# PLC1_4.net
KiCad netlist of a schematic drawn in Altium Designer
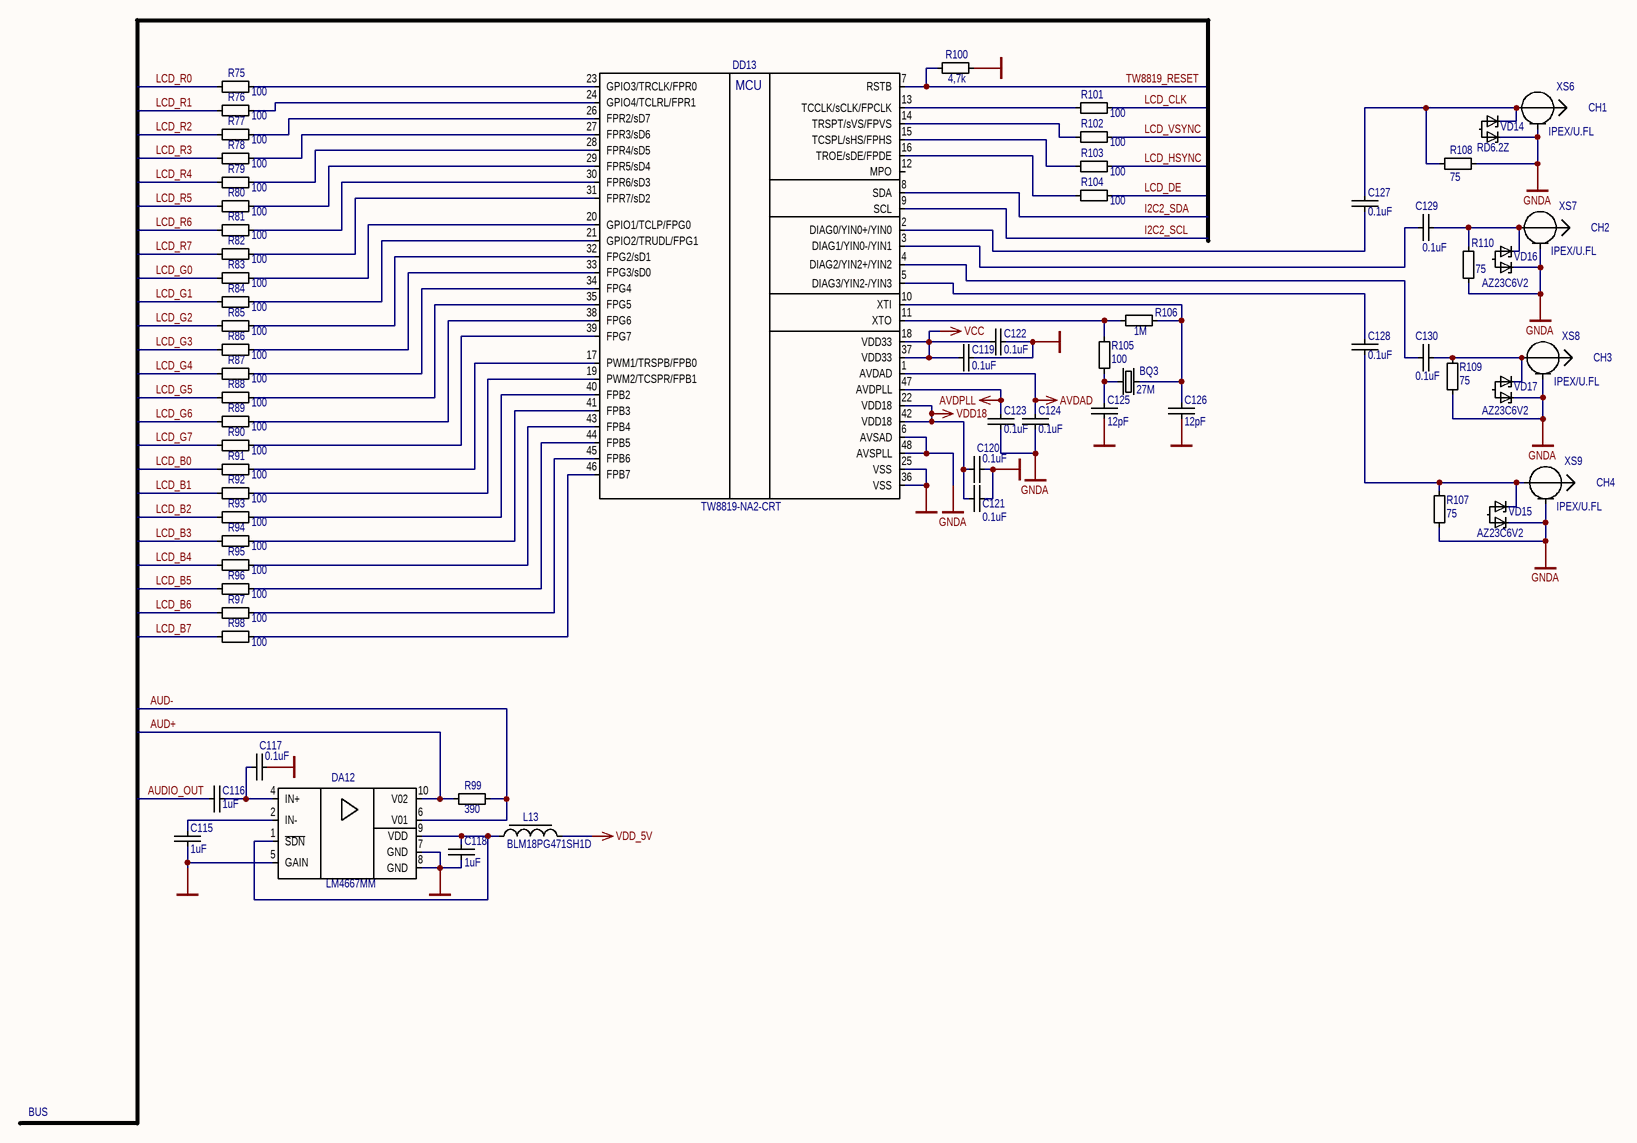
[diagram p0: PLC1_4.SchDoc]

(export (version "E")
  (design (tool "Eeschema 10.0.6"))
  (components
    (comp (ref "BQ3")
      (value "27M")
      (footprint "TSX-3225")
      (fields
        (field (name "MANUFACTURER") "EPSON")
        (field (name "PART NUMBER") "EPSON TSX-3225 27.0000MF10Z-K3")
        (field (name "Comment") "TSX-3225")
      )
      (libsource (lib "PLC1") (part "TSX-3225"))
    )
    (comp (ref "C115")
      (value "1uF")
      (footprint "CAP_0603")
      (fields (field (name "MANUFACTURER") "AVX") (field (name "PART NUMBER") "0603YC105KAT2A"))
      (libsource (lib "PLC1") (part "Cap_0603"))
    )
    (comp (ref "C116")
      (value "1uF")
      (footprint "CAP_0603")
      (fields (field (name "MANUFACTURER") "AVX") (field (name "PART NUMBER") "0603YC105KAT2A"))
      (libsource (lib "PLC1") (part "Cap_0603"))
    )
    (comp (ref "C117")
      (value "0.1uF")
      (footprint "CAP_0603")
      (fields (field (name "MANUFACTURER") "AVX") (field (name "PART NUMBER") "0603YC104KAT2A"))
      (libsource (lib "PLC1") (part "Cap_0603"))
    )
    (comp (ref "C118")
      (value "1uF")
      (footprint "CAP_0603")
      (fields (field (name "MANUFACTURER") "AVX") (field (name "PART NUMBER") "0603YC105KAT2A"))
      (libsource (lib "PLC1") (part "Cap_0603"))
    )
    (comp (ref "C119")
      (value "0.1uF")
      (footprint "CAP_0603")
      (fields (field (name "MANUFACTURER") "AVX") (field (name "PART NUMBER") "0603YC104KAT2A"))
      (libsource (lib "PLC1") (part "Cap_0603"))
    )
    (comp (ref "C120")
      (value "0.1uF")
      (footprint "CAP_0603")
      (fields (field (name "MANUFACTURER") "AVX") (field (name "PART NUMBER") "0603YC104KAT2A"))
      (libsource (lib "PLC1") (part "Cap_0603"))
    )
    (comp (ref "C121")
      (value "0.1uF")
      (footprint "CAP_0603")
      (fields (field (name "MANUFACTURER") "AVX") (field (name "PART NUMBER") "0603YC104KAT2A"))
      (libsource (lib "PLC1") (part "Cap_0603"))
    )
    (comp (ref "C122")
      (value "0.1uF")
      (footprint "CAP_0603")
      (fields (field (name "MANUFACTURER") "AVX") (field (name "PART NUMBER") "0603YC104KAT2A"))
      (libsource (lib "PLC1") (part "Cap_0603"))
    )
    (comp (ref "C123")
      (value "0.1uF")
      (footprint "CAP_0603")
      (fields (field (name "MANUFACTURER") "AVX") (field (name "PART NUMBER") "0603YC104KAT2A"))
      (libsource (lib "PLC1") (part "Cap_0603"))
    )
    (comp (ref "C124")
      (value "0.1uF")
      (footprint "CAP_0603")
      (fields (field (name "MANUFACTURER") "AVX") (field (name "PART NUMBER") "0603YC104KAT2A"))
      (libsource (lib "PLC1") (part "Cap_0603"))
    )
    (comp (ref "C125")
      (value "12pF")
      (footprint "CAP_0603")
      (fields (field (name "MANUFACTURER") "Murata") (field (name "PART NUMBER") "GRM1885C1H120JA01D"))
      (libsource (lib "PLC1") (part "Cap_0603"))
    )
    (comp (ref "C126")
      (value "12pF")
      (footprint "CAP_0603")
      (fields (field (name "MANUFACTURER") "Murata") (field (name "PART NUMBER") "GRM1885C1H120JA01D"))
      (libsource (lib "PLC1") (part "Cap_0603"))
    )
    (comp (ref "C127")
      (value "0.1uF")
      (footprint "CAP_0603")
      (fields (field (name "MANUFACTURER") "AVX") (field (name "PART NUMBER") "0603YC104KAT2A"))
      (libsource (lib "PLC1") (part "Cap_0603"))
    )
    (comp (ref "C128")
      (value "0.1uF")
      (footprint "CAP_0603")
      (fields (field (name "MANUFACTURER") "AVX") (field (name "PART NUMBER") "0603YC104KAT2A"))
      (libsource (lib "PLC1") (part "Cap_0603"))
    )
    (comp (ref "C129")
      (value "0.1uF")
      (footprint "CAP_0603")
      (fields (field (name "MANUFACTURER") "AVX") (field (name "PART NUMBER") "0603YC104KAT2A"))
      (libsource (lib "PLC1") (part "Cap_0603"))
    )
    (comp (ref "C130")
      (value "0.1uF")
      (footprint "CAP_0603")
      (fields (field (name "MANUFACTURER") "AVX") (field (name "PART NUMBER") "0603YC104KAT2A"))
      (libsource (lib "PLC1") (part "Cap_0603"))
    )
    (comp (ref "DA12")
      (value "LM4667MM")
      (footprint "S-PDSO-G10")
      (description "LM4667MM/NOPB")
      (fields (field (name "MANUFACTURER") "TEXAS INSTRUMENTS"))
      (libsource (lib "PLC1") (part "LM4667MM/NOPB"))
    )
    (comp (ref "DD13")
      (value "TW8819-NA2-CRT")
      (footprint "QFN48.7x7")
      (fields (field (name "MANUFACTURER") "Intersil") (field (name "TW8819-NA2-CRT") "TW8819-NA2-CRT"))
      (libsource (lib "PLC1") (part "TW8819-NA2-CRT"))
    )
    (comp (ref "L13")
      (value "BLM18PG471SH1D")
      (footprint "R_IND_0603")
      (fields (field (name "MANUFACTURER") "Murata"))
      (libsource (lib "PLC1") (part "FCM1608KF-601T03"))
    )
    (comp (ref "R75")
      (value "100")
      (footprint "RES_0402")
      (description "0402")
      (fields (field (name "MANUFACTURER") "BOURNS") (field (name "PART NUMBER") "CR0402-FX-1000GLF"))
      (libsource (lib "PLC1") (part "Res_0402"))
    )
    (comp (ref "R76")
      (value "100")
      (footprint "RES_0402")
      (description "0402")
      (fields (field (name "MANUFACTURER") "BOURNS") (field (name "PART NUMBER") "CR0402-FX-1000GLF"))
      (libsource (lib "PLC1") (part "Res_0402"))
    )
    (comp (ref "R77")
      (value "100")
      (footprint "RES_0402")
      (description "0402")
      (fields (field (name "MANUFACTURER") "BOURNS") (field (name "PART NUMBER") "CR0402-FX-1000GLF"))
      (libsource (lib "PLC1") (part "Res_0402"))
    )
    (comp (ref "R78")
      (value "100")
      (footprint "RES_0402")
      (description "0402")
      (fields (field (name "MANUFACTURER") "BOURNS") (field (name "PART NUMBER") "CR0402-FX-1000GLF"))
      (libsource (lib "PLC1") (part "Res_0402"))
    )
    (comp (ref "R79")
      (value "100")
      (footprint "RES_0402")
      (description "0402")
      (fields (field (name "MANUFACTURER") "BOURNS") (field (name "PART NUMBER") "CR0402-FX-1000GLF"))
      (libsource (lib "PLC1") (part "Res_0402"))
    )
    (comp (ref "R80")
      (value "100")
      (footprint "RES_0402")
      (description "0402")
      (fields (field (name "MANUFACTURER") "BOURNS") (field (name "PART NUMBER") "CR0402-FX-1000GLF"))
      (libsource (lib "PLC1") (part "Res_0402"))
    )
    (comp (ref "R81")
      (value "100")
      (footprint "RES_0402")
      (description "0402")
      (fields (field (name "MANUFACTURER") "BOURNS") (field (name "PART NUMBER") "CR0402-FX-1000GLF"))
      (libsource (lib "PLC1") (part "Res_0402"))
    )
    (comp (ref "R82")
      (value "100")
      (footprint "RES_0402")
      (description "0402")
      (fields (field (name "MANUFACTURER") "BOURNS") (field (name "PART NUMBER") "CR0402-FX-1000GLF"))
      (libsource (lib "PLC1") (part "Res_0402"))
    )
    (comp (ref "R83")
      (value "100")
      (footprint "RES_0402")
      (description "0402")
      (fields (field (name "MANUFACTURER") "BOURNS") (field (name "PART NUMBER") "CR0402-FX-1000GLF"))
      (libsource (lib "PLC1") (part "Res_0402"))
    )
    (comp (ref "R84")
      (value "100")
      (footprint "RES_0402")
      (description "0402")
      (fields (field (name "MANUFACTURER") "BOURNS") (field (name "PART NUMBER") "CR0402-FX-1000GLF"))
      (libsource (lib "PLC1") (part "Res_0402"))
    )
    (comp (ref "R85")
      (value "100")
      (footprint "RES_0402")
      (description "0402")
      (fields (field (name "MANUFACTURER") "BOURNS") (field (name "PART NUMBER") "CR0402-FX-1000GLF"))
      (libsource (lib "PLC1") (part "Res_0402"))
    )
    (comp (ref "R86")
      (value "100")
      (footprint "RES_0402")
      (description "0402")
      (fields (field (name "MANUFACTURER") "BOURNS") (field (name "PART NUMBER") "CR0402-FX-1000GLF"))
      (libsource (lib "PLC1") (part "Res_0402"))
    )
    (comp (ref "R87")
      (value "100")
      (footprint "RES_0402")
      (description "0402")
      (fields (field (name "MANUFACTURER") "BOURNS") (field (name "PART NUMBER") "CR0402-FX-1000GLF"))
      (libsource (lib "PLC1") (part "Res_0402"))
    )
    (comp (ref "R88")
      (value "100")
      (footprint "RES_0402")
      (description "0402")
      (fields (field (name "MANUFACTURER") "BOURNS") (field (name "PART NUMBER") "CR0402-FX-1000GLF"))
      (libsource (lib "PLC1") (part "Res_0402"))
    )
    (comp (ref "R89")
      (value "100")
      (footprint "RES_0402")
      (description "0402")
      (fields (field (name "MANUFACTURER") "BOURNS") (field (name "PART NUMBER") "CR0402-FX-1000GLF"))
      (libsource (lib "PLC1") (part "Res_0402"))
    )
    (comp (ref "R90")
      (value "100")
      (footprint "RES_0402")
      (description "0402")
      (fields (field (name "MANUFACTURER") "BOURNS") (field (name "PART NUMBER") "CR0402-FX-1000GLF"))
      (libsource (lib "PLC1") (part "Res_0402"))
    )
    (comp (ref "R91")
      (value "100")
      (footprint "RES_0402")
      (description "0402")
      (fields (field (name "MANUFACTURER") "BOURNS") (field (name "PART NUMBER") "CR0402-FX-1000GLF"))
      (libsource (lib "PLC1") (part "Res_0402"))
    )
    (comp (ref "R92")
      (value "100")
      (footprint "RES_0402")
      (description "0402")
      (fields (field (name "MANUFACTURER") "BOURNS") (field (name "PART NUMBER") "CR0402-FX-1000GLF"))
      (libsource (lib "PLC1") (part "Res_0402"))
    )
    (comp (ref "R93")
      (value "100")
      (footprint "RES_0402")
      (description "0402")
      (fields (field (name "MANUFACTURER") "BOURNS") (field (name "PART NUMBER") "CR0402-FX-1000GLF"))
      (libsource (lib "PLC1") (part "Res_0402"))
    )
    (comp (ref "R94")
      (value "100")
      (footprint "RES_0402")
      (description "0402")
      (fields (field (name "MANUFACTURER") "BOURNS") (field (name "PART NUMBER") "CR0402-FX-1000GLF"))
      (libsource (lib "PLC1") (part "Res_0402"))
    )
    (comp (ref "R95")
      (value "100")
      (footprint "RES_0402")
      (description "0402")
      (fields (field (name "MANUFACTURER") "BOURNS") (field (name "PART NUMBER") "CR0402-FX-1000GLF"))
      (libsource (lib "PLC1") (part "Res_0402"))
    )
    (comp (ref "R96")
      (value "100")
      (footprint "RES_0402")
      (description "0402")
      (fields (field (name "MANUFACTURER") "BOURNS") (field (name "PART NUMBER") "CR0402-FX-1000GLF"))
      (libsource (lib "PLC1") (part "Res_0402"))
    )
    (comp (ref "R97")
      (value "100")
      (footprint "RES_0402")
      (description "0402")
      (fields (field (name "MANUFACTURER") "BOURNS") (field (name "PART NUMBER") "CR0402-FX-1000GLF"))
      (libsource (lib "PLC1") (part "Res_0402"))
    )
    (comp (ref "R98")
      (value "100")
      (footprint "RES_0402")
      (description "0402")
      (fields (field (name "MANUFACTURER") "BOURNS") (field (name "PART NUMBER") "CR0402-FX-1000GLF"))
      (libsource (lib "PLC1") (part "Res_0402"))
    )
    (comp (ref "R99")
      (value "390")
      (footprint "RES_0603")
      (description "0603, 390")
      (fields (field (name "MANUFACTURER") "YAGEO") (field (name "PART NUMBER") "RC0603FR-07390RL"))
      (libsource (lib "PLC1") (part "Res_0603"))
    )
    (comp (ref "R100")
      (value "4,7k")
      (footprint "RES_0603")
      (description "0603, 100")
      (fields (field (name "MANUFACTURER") "Vishay") (field (name "PART NUMBER") "CRCW0603-472JRT1"))
      (libsource (lib "PLC1") (part "Res_0603"))
    )
    (comp (ref "R101")
      (value "100")
      (footprint "RES_0402")
      (description "0402")
      (fields (field (name "MANUFACTURER") "BOURNS") (field (name "PART NUMBER") "CR0402-FX-1000GLF"))
      (libsource (lib "PLC1") (part "Res_0402"))
    )
    (comp (ref "R102")
      (value "100")
      (footprint "RES_0402")
      (description "0402")
      (fields (field (name "MANUFACTURER") "BOURNS") (field (name "PART NUMBER") "CR0402-FX-1000GLF"))
      (libsource (lib "PLC1") (part "Res_0402"))
    )
    (comp (ref "R103")
      (value "100")
      (footprint "RES_0402")
      (description "0402")
      (fields (field (name "MANUFACTURER") "BOURNS") (field (name "PART NUMBER") "CR0402-FX-1000GLF"))
      (libsource (lib "PLC1") (part "Res_0402"))
    )
    (comp (ref "R104")
      (value "100")
      (footprint "RES_0402")
      (description "0402")
      (fields (field (name "MANUFACTURER") "BOURNS") (field (name "PART NUMBER") "CR0402-FX-1000GLF"))
      (libsource (lib "PLC1") (part "Res_0402"))
    )
    (comp (ref "R105")
      (value "100")
      (footprint "RES_0402")
      (description "0402")
      (fields (field (name "MANUFACTURER") "BOURNS") (field (name "PART NUMBER") "CR0402-FX-1000GLF"))
      (libsource (lib "PLC1") (part "Res_0402"))
    )
    (comp (ref "R106")
      (value "1M")
      (footprint "RES_0402")
      (description "0402")
      (fields (field (name "MANUFACTURER") "BOURNS") (field (name "PART NUMBER") "RC0402JR-071ML"))
      (libsource (lib "PLC1") (part "Res_0402"))
    )
    (comp (ref "R107")
      (value "75")
      (footprint "RES_0603")
      (description "0603")
      (fields (field (name "MANUFACTURER") "YAGEO") (field (name "PART NUMBER") "RC0603JR-0775RL"))
      (libsource (lib "PLC1") (part "Res_0603"))
    )
    (comp (ref "R108")
      (value "75")
      (footprint "RES_0603")
      (description "0603")
      (fields (field (name "MANUFACTURER") "YAGEO") (field (name "PART NUMBER") "RC0603JR-0775RL"))
      (libsource (lib "PLC1") (part "Res_0603"))
    )
    (comp (ref "R109")
      (value "75")
      (footprint "RES_0603")
      (description "0603")
      (fields (field (name "MANUFACTURER") "YAGEO") (field (name "PART NUMBER") "RC0603JR-0775RL"))
      (libsource (lib "PLC1") (part "Res_0603"))
    )
    (comp (ref "R110")
      (value "75")
      (footprint "RES_0603")
      (description "0603")
      (fields (field (name "MANUFACTURER") "YAGEO") (field (name "PART NUMBER") "RC0603JR-0775RL"))
      (libsource (lib "PLC1") (part "Res_0603"))
    )
    (comp (ref "VD14")
      (value "RD6.2Z")
      (footprint "SC-59")
      (fields (field (name "MANUFACTURER") "NEC"))
      (libsource (lib "PLC1") (part "RD6.2Z"))
    )
    (comp (ref "VD15")
      (value "RD6.2Z")
      (footprint "SC-59")
      (fields (field (name "PART NUMBER") "AZ23C6V2") (field (name "MANUFACTURER") "NEC"))
      (libsource (lib "PLC1") (part "RD6.2Z"))
    )
    (comp (ref "VD16")
      (value "RD6.2Z")
      (footprint "SC-59")
      (fields (field (name "PART NUMBER") "AZ23C6V2") (field (name "MANUFACTURER") "NEC"))
      (libsource (lib "PLC1") (part "RD6.2Z"))
    )
    (comp (ref "VD17")
      (value "RD6.2Z")
      (footprint "SC-59")
      (fields (field (name "PART NUMBER") "AZ23C6V2") (field (name "MANUFACTURER") "NEC"))
      (libsource (lib "PLC1") (part "RD6.2Z"))
    )
    (comp (ref "XS6")
      (value "IPEX/U.FL")
      (footprint "IPEX MHFI")
      (description "IPEX/U.FL male pcb SMT")
      (fields
        (field (name "MANUFACTURER") "taoglas limited")
        (field (name "PACKAGEREFERENCE") "IPEX/U.FL")
        (field (name "PART NUMBER") "20279-001E-01")
      )
      (libsource (lib "PLC1") (part "IPEX/U.FL"))
    )
    (comp (ref "XS7")
      (value "IPEX/U.FL")
      (footprint "IPEX MHFI")
      (description "IPEX/U.FL male pcb SMT")
      (fields
        (field (name "MANUFACTURER") "taoglas limited")
        (field (name "PACKAGEREFERENCE") "IPEX/U.FL")
        (field (name "PART NUMBER") "20279-001E-01")
      )
      (libsource (lib "PLC1") (part "IPEX/U.FL"))
    )
    (comp (ref "XS8")
      (value "IPEX/U.FL")
      (footprint "IPEX MHFI")
      (description "IPEX/U.FL male pcb SMT")
      (fields
        (field (name "MANUFACTURER") "taoglas limited")
        (field (name "PACKAGEREFERENCE") "IPEX/U.FL")
        (field (name "PART NUMBER") "20279-001E-01")
      )
      (libsource (lib "PLC1") (part "IPEX/U.FL"))
    )
    (comp (ref "XS9")
      (value "IPEX/U.FL")
      (footprint "IPEX MHFI")
      (description "IPEX/U.FL male pcb SMT")
      (fields
        (field (name "MANUFACTURER") "taoglas limited")
        (field (name "PACKAGEREFERENCE") "IPEX/U.FL")
        (field (name "PART NUMBER") "20279-001E-01")
      )
      (libsource (lib "PLC1") (part "IPEX/U.FL"))
    )
  )
  (nets
    (net (code "1") (name "/AUD+") (class "Default")
      (node (ref "DA12") (pin "10") (pinfunction "V02_10") (pintype "passive"))
      (node (ref "R99") (pin "2") (pinfunction "2_2") (pintype "passive"))
    )
    (net (code "2") (name "/AUD-") (class "Default")
      (node (ref "DA12") (pin "6") (pinfunction "V01_6") (pintype "passive"))
      (node (ref "R99") (pin "1") (pinfunction "1_1") (pintype "passive"))
    )
    (net (code "3") (name "/AUDIO_OUT") (class "Default")
      (node (ref "C116") (pin "2") (pinfunction "2_2") (pintype "passive"))
    )
    (net (code "4") (name "/I2C2_SCL") (class "Default")
      (node (ref "DD13") (pin "9") (pinfunction "SCL_9") (pintype "passive"))
    )
    (net (code "5") (name "/I2C2_SDA") (class "Default")
      (node (ref "DD13") (pin "8") (pinfunction "SDA_8") (pintype "passive"))
    )
    (net (code "6") (name "/LCD_B0") (class "Default")
      (node (ref "R91") (pin "2") (pinfunction "2_2") (pintype "passive"))
    )
    (net (code "7") (name "/LCD_B1") (class "Default")
      (node (ref "R92") (pin "2") (pinfunction "2_2") (pintype "passive"))
    )
    (net (code "8") (name "/LCD_B2") (class "Default")
      (node (ref "R93") (pin "2") (pinfunction "2_2") (pintype "passive"))
    )
    (net (code "9") (name "/LCD_B3") (class "Default")
      (node (ref "R94") (pin "2") (pinfunction "2_2") (pintype "passive"))
    )
    (net (code "10") (name "/LCD_B4") (class "Default")
      (node (ref "R95") (pin "2") (pinfunction "2_2") (pintype "passive"))
    )
    (net (code "11") (name "/LCD_B5") (class "Default")
      (node (ref "R96") (pin "2") (pinfunction "2_2") (pintype "passive"))
    )
    (net (code "12") (name "/LCD_B6") (class "Default")
      (node (ref "R97") (pin "2") (pinfunction "2_2") (pintype "passive"))
    )
    (net (code "13") (name "/LCD_B7") (class "Default")
      (node (ref "R98") (pin "2") (pinfunction "2_2") (pintype "passive"))
    )
    (net (code "14") (name "/LCD_CLK") (class "Default")
      (node (ref "R101") (pin "2") (pinfunction "2_2") (pintype "passive"))
    )
    (net (code "15") (name "/LCD_DE") (class "Default")
      (node (ref "R104") (pin "2") (pinfunction "2_2") (pintype "passive"))
    )
    (net (code "16") (name "/LCD_G0") (class "Default")
      (node (ref "R83") (pin "2") (pinfunction "2_2") (pintype "passive"))
    )
    (net (code "17") (name "/LCD_G1") (class "Default")
      (node (ref "R84") (pin "2") (pinfunction "2_2") (pintype "passive"))
    )
    (net (code "18") (name "/LCD_G2") (class "Default")
      (node (ref "R85") (pin "2") (pinfunction "2_2") (pintype "passive"))
    )
    (net (code "19") (name "/LCD_G3") (class "Default")
      (node (ref "R86") (pin "2") (pinfunction "2_2") (pintype "passive"))
    )
    (net (code "20") (name "/LCD_G4") (class "Default")
      (node (ref "R87") (pin "2") (pinfunction "2_2") (pintype "passive"))
    )
    (net (code "21") (name "/LCD_G5") (class "Default")
      (node (ref "R88") (pin "2") (pinfunction "2_2") (pintype "passive"))
    )
    (net (code "22") (name "/LCD_G6") (class "Default")
      (node (ref "R89") (pin "2") (pinfunction "2_2") (pintype "passive"))
    )
    (net (code "23") (name "/LCD_G7") (class "Default")
      (node (ref "R90") (pin "2") (pinfunction "2_2") (pintype "passive"))
    )
    (net (code "24") (name "/LCD_HSYNC") (class "Default")
      (node (ref "R103") (pin "2") (pinfunction "2_2") (pintype "passive"))
    )
    (net (code "25") (name "/LCD_R0") (class "Default")
      (node (ref "R75") (pin "2") (pinfunction "2_2") (pintype "passive"))
    )
    (net (code "26") (name "/LCD_R1") (class "Default")
      (node (ref "R76") (pin "2") (pinfunction "2_2") (pintype "passive"))
    )
    (net (code "27") (name "/LCD_R2") (class "Default")
      (node (ref "R77") (pin "2") (pinfunction "2_2") (pintype "passive"))
    )
    (net (code "28") (name "/LCD_R3") (class "Default")
      (node (ref "R78") (pin "2") (pinfunction "2_2") (pintype "passive"))
    )
    (net (code "29") (name "/LCD_R4") (class "Default")
      (node (ref "R79") (pin "2") (pinfunction "2_2") (pintype "passive"))
    )
    (net (code "30") (name "/LCD_R5") (class "Default")
      (node (ref "R80") (pin "2") (pinfunction "2_2") (pintype "passive"))
    )
    (net (code "31") (name "/LCD_R6") (class "Default")
      (node (ref "R81") (pin "2") (pinfunction "2_2") (pintype "passive"))
    )
    (net (code "32") (name "/LCD_R7") (class "Default")
      (node (ref "R82") (pin "2") (pinfunction "2_2") (pintype "passive"))
    )
    (net (code "33") (name "/LCD_VSYNC") (class "Default")
      (node (ref "R102") (pin "2") (pinfunction "2_2") (pintype "passive"))
    )
    (net (code "34") (name "/TW8819_RESET") (class "Default")
      (node (ref "DD13") (pin "7") (pinfunction "RSTB_7") (pintype "passive"))
      (node (ref "R100") (pin "1") (pinfunction "1_1") (pintype "passive"))
    )
    (net (code "35") (name "AVDAD") (class "Default")
      (node (ref "C124") (pin "1") (pinfunction "1_1") (pintype "passive"))
      (node (ref "DD13") (pin "1") (pinfunction "AVDAD_1") (pintype "passive"))
    )
    (net (code "36") (name "AVDPLL") (class "Default")
      (node (ref "C123") (pin "1") (pinfunction "1_1") (pintype "passive"))
      (node (ref "DD13") (pin "47") (pinfunction "AVDPLL_47") (pintype "passive"))
    )
    (net (code "37") (name "GND") (class "Default")
      (node (ref "C115") (pin "1") (pinfunction "1_1") (pintype "passive"))
      (node (ref "C117") (pin "2") (pinfunction "2_2") (pintype "passive"))
      (node (ref "C118") (pin "1") (pinfunction "1_1") (pintype "passive"))
      (node (ref "C119") (pin "2") (pinfunction "2_2") (pintype "passive"))
      (node (ref "C120") (pin "2") (pinfunction "2_2") (pintype "passive"))
      (node (ref "C121") (pin "2") (pinfunction "2_2") (pintype "passive"))
      (node (ref "C122") (pin "2") (pinfunction "2_2") (pintype "passive"))
      (node (ref "C125") (pin "1") (pinfunction "1_1") (pintype "passive"))
      (node (ref "C126") (pin "1") (pinfunction "1_1") (pintype "passive"))
      (node (ref "DA12") (pin "5") (pinfunction "GAIN_5") (pintype "passive"))
      (node (ref "DA12") (pin "7") (pinfunction "GND_7") (pintype "passive"))
      (node (ref "DA12") (pin "8") (pinfunction "GND_8") (pintype "passive"))
      (node (ref "DD13") (pin "25") (pinfunction "VSS_25") (pintype "passive"))
      (node (ref "DD13") (pin "36") (pinfunction "VSS_36") (pintype "passive"))
      (node (ref "R100") (pin "2") (pinfunction "2_2") (pintype "passive"))
    )
    (net (code "38") (name "GNDA") (class "Default")
      (node (ref "C123") (pin "2") (pinfunction "2_2") (pintype "passive"))
      (node (ref "C124") (pin "2") (pinfunction "2_2") (pintype "passive"))
      (node (ref "DD13") (pin "48") (pinfunction "AVSPLL_48") (pintype "passive"))
      (node (ref "DD13") (pin "6") (pinfunction "AVSAD_6") (pintype "passive"))
      (node (ref "R107") (pin "1") (pinfunction "1_1") (pintype "passive"))
      (node (ref "R108") (pin "2") (pinfunction "2_2") (pintype "passive"))
      (node (ref "R109") (pin "1") (pinfunction "1_1") (pintype "passive"))
      (node (ref "R110") (pin "2") (pinfunction "2_2") (pintype "passive"))
      (node (ref "VD14") (pin "2") (pinfunction "2_2") (pintype "passive"))
      (node (ref "VD15") (pin "2") (pinfunction "2_2") (pintype "passive"))
      (node (ref "VD16") (pin "2") (pinfunction "2_2") (pintype "passive"))
      (node (ref "VD17") (pin "2") (pinfunction "2_2") (pintype "passive"))
      (node (ref "XS6") (pin "2") (pinfunction "2_2") (pintype "passive"))
      (node (ref "XS7") (pin "2") (pinfunction "2_2") (pintype "passive"))
      (node (ref "XS8") (pin "2") (pinfunction "2_2") (pintype "passive"))
      (node (ref "XS9") (pin "2") (pinfunction "2_2") (pintype "passive"))
    )
    (net (code "39") (name "Net-(BQ3-Pad2)") (class "Default")
      (node (ref "BQ3") (pin "2") (pinfunction "2_2") (pintype "passive"))
      (node (ref "C125") (pin "2") (pinfunction "2_2") (pintype "passive"))
      (node (ref "R105") (pin "1") (pinfunction "1_1") (pintype "passive"))
    )
    (net (code "40") (name "Net-(C127-Pad1)") (class "Default")
      (node (ref "C127") (pin "1") (pinfunction "1_1") (pintype "passive"))
      (node (ref "R108") (pin "1") (pinfunction "1_1") (pintype "passive"))
      (node (ref "VD14") (pin "1") (pinfunction "1_1") (pintype "passive"))
      (node (ref "XS6") (pin "1") (pinfunction "1_1") (pintype "passive"))
    )
    (net (code "41") (name "Net-(C128-Pad2)") (class "Default")
      (node (ref "C128") (pin "2") (pinfunction "2_2") (pintype "passive"))
      (node (ref "R107") (pin "2") (pinfunction "2_2") (pintype "passive"))
      (node (ref "VD15") (pin "1") (pinfunction "1_1") (pintype "passive"))
      (node (ref "XS9") (pin "1") (pinfunction "1_1") (pintype "passive"))
    )
    (net (code "42") (name "Net-(C129-Pad2)") (class "Default")
      (node (ref "C129") (pin "2") (pinfunction "2_2") (pintype "passive"))
      (node (ref "R110") (pin "1") (pinfunction "1_1") (pintype "passive"))
      (node (ref "VD16") (pin "1") (pinfunction "1_1") (pintype "passive"))
      (node (ref "XS7") (pin "1") (pinfunction "1_1") (pintype "passive"))
    )
    (net (code "43") (name "Net-(C130-Pad2)") (class "Default")
      (node (ref "C130") (pin "2") (pinfunction "2_2") (pintype "passive"))
      (node (ref "R109") (pin "2") (pinfunction "2_2") (pintype "passive"))
      (node (ref "VD17") (pin "1") (pinfunction "1_1") (pintype "passive"))
      (node (ref "XS8") (pin "1") (pinfunction "1_1") (pintype "passive"))
    )
    (net (code "44") (name "Net-(DA12-IN+)") (class "Default")
      (node (ref "C116") (pin "1") (pinfunction "1_1") (pintype "passive"))
      (node (ref "C117") (pin "1") (pinfunction "1_1") (pintype "passive"))
      (node (ref "DA12") (pin "4") (pinfunction "IN+_4") (pintype "passive"))
    )
    (net (code "45") (name "Net-(DA12-IN-)") (class "Default")
      (node (ref "C115") (pin "2") (pinfunction "2_2") (pintype "passive"))
      (node (ref "DA12") (pin "2") (pinfunction "IN-_2") (pintype "passive"))
    )
    (net (code "46") (name "Net-(DA12-VDD)") (class "Default")
      (node (ref "C118") (pin "2") (pinfunction "2_2") (pintype "passive"))
      (node (ref "DA12") (pin "1") (pinfunction "~{SDN}_1") (pintype "passive"))
      (node (ref "DA12") (pin "9") (pinfunction "VDD_9") (pintype "passive"))
      (node (ref "L13") (pin "2") (pinfunction "2_2") (pintype "passive"))
    )
    (net (code "47") (name "Net-(DD13-DIAG0{slash}YIN0+{slash}YIN0)") (class "Default")
      (node (ref "C127") (pin "2") (pinfunction "2_2") (pintype "passive"))
      (node (ref "DD13") (pin "2") (pinfunction "DIAG0/YIN0+/YIN0_2") (pintype "passive"))
    )
    (net (code "48") (name "Net-(DD13-DIAG1{slash}YIN0-{slash}YIN1)") (class "Default")
      (node (ref "C129") (pin "1") (pinfunction "1_1") (pintype "passive"))
      (node (ref "DD13") (pin "3") (pinfunction "DIAG1/YIN0-/YIN1_3") (pintype "passive"))
    )
    (net (code "49") (name "Net-(DD13-DIAG2{slash}YIN2+{slash}YIN2)") (class "Default")
      (node (ref "C130") (pin "1") (pinfunction "1_1") (pintype "passive"))
      (node (ref "DD13") (pin "4") (pinfunction "DIAG2/YIN2+/YIN2_4") (pintype "passive"))
    )
    (net (code "50") (name "Net-(DD13-DIAG3{slash}YIN2-{slash}YIN3)") (class "Default")
      (node (ref "C128") (pin "1") (pinfunction "1_1") (pintype "passive"))
      (node (ref "DD13") (pin "5") (pinfunction "DIAG3/YIN2-/YIN3_5") (pintype "passive"))
    )
    (net (code "51") (name "Net-(DD13-FPB2)") (class "Default")
      (node (ref "DD13") (pin "40") (pinfunction "FPB2_40") (pintype "passive"))
      (node (ref "R93") (pin "1") (pinfunction "1_1") (pintype "passive"))
    )
    (net (code "52") (name "Net-(DD13-FPB3)") (class "Default")
      (node (ref "DD13") (pin "41") (pinfunction "FPB3_41") (pintype "passive"))
      (node (ref "R94") (pin "1") (pinfunction "1_1") (pintype "passive"))
    )
    (net (code "53") (name "Net-(DD13-FPB4)") (class "Default")
      (node (ref "DD13") (pin "43") (pinfunction "FPB4_43") (pintype "passive"))
      (node (ref "R95") (pin "1") (pinfunction "1_1") (pintype "passive"))
    )
    (net (code "54") (name "Net-(DD13-FPB5)") (class "Default")
      (node (ref "DD13") (pin "44") (pinfunction "FPB5_44") (pintype "passive"))
      (node (ref "R96") (pin "1") (pinfunction "1_1") (pintype "passive"))
    )
    (net (code "55") (name "Net-(DD13-FPB6)") (class "Default")
      (node (ref "DD13") (pin "45") (pinfunction "FPB6_45") (pintype "passive"))
      (node (ref "R97") (pin "1") (pinfunction "1_1") (pintype "passive"))
    )
    (net (code "56") (name "Net-(DD13-FPB7)") (class "Default")
      (node (ref "DD13") (pin "46") (pinfunction "FPB7_46") (pintype "passive"))
      (node (ref "R98") (pin "1") (pinfunction "1_1") (pintype "passive"))
    )
    (net (code "57") (name "Net-(DD13-FPG2{slash}sD1)") (class "Default")
      (node (ref "DD13") (pin "32") (pinfunction "FPG2/sD1_32") (pintype "passive"))
      (node (ref "R85") (pin "1") (pinfunction "1_1") (pintype "passive"))
    )
    (net (code "58") (name "Net-(DD13-FPG3{slash}sD0)") (class "Default")
      (node (ref "DD13") (pin "33") (pinfunction "FPG3/sD0_33") (pintype "passive"))
      (node (ref "R86") (pin "1") (pinfunction "1_1") (pintype "passive"))
    )
    (net (code "59") (name "Net-(DD13-FPG4)") (class "Default")
      (node (ref "DD13") (pin "34") (pinfunction "FPG4_34") (pintype "passive"))
      (node (ref "R87") (pin "1") (pinfunction "1_1") (pintype "passive"))
    )
    (net (code "60") (name "Net-(DD13-FPG5)") (class "Default")
      (node (ref "DD13") (pin "35") (pinfunction "FPG5_35") (pintype "passive"))
      (node (ref "R88") (pin "1") (pinfunction "1_1") (pintype "passive"))
    )
    (net (code "61") (name "Net-(DD13-FPG6)") (class "Default")
      (node (ref "DD13") (pin "38") (pinfunction "FPG6_38") (pintype "passive"))
      (node (ref "R89") (pin "1") (pinfunction "1_1") (pintype "passive"))
    )
    (net (code "62") (name "Net-(DD13-FPG7)") (class "Default")
      (node (ref "DD13") (pin "39") (pinfunction "FPG7_39") (pintype "passive"))
      (node (ref "R90") (pin "1") (pinfunction "1_1") (pintype "passive"))
    )
    (net (code "63") (name "Net-(DD13-FPR2{slash}sD7)") (class "Default")
      (node (ref "DD13") (pin "26") (pinfunction "FPR2/sD7_26") (pintype "passive"))
      (node (ref "R77") (pin "1") (pinfunction "1_1") (pintype "passive"))
    )
    (net (code "64") (name "Net-(DD13-FPR3{slash}sD6)") (class "Default")
      (node (ref "DD13") (pin "27") (pinfunction "FPR3/sD6_27") (pintype "passive"))
      (node (ref "R78") (pin "1") (pinfunction "1_1") (pintype "passive"))
    )
    (net (code "65") (name "Net-(DD13-FPR4{slash}sD5)") (class "Default")
      (node (ref "DD13") (pin "28") (pinfunction "FPR4/sD5_28") (pintype "passive"))
      (node (ref "R79") (pin "1") (pinfunction "1_1") (pintype "passive"))
    )
    (net (code "66") (name "Net-(DD13-FPR5{slash}sD4)") (class "Default")
      (node (ref "DD13") (pin "29") (pinfunction "FPR5/sD4_29") (pintype "passive"))
      (node (ref "R80") (pin "1") (pinfunction "1_1") (pintype "passive"))
    )
    (net (code "67") (name "Net-(DD13-FPR6{slash}sD3)") (class "Default")
      (node (ref "DD13") (pin "30") (pinfunction "FPR6/sD3_30") (pintype "passive"))
      (node (ref "R81") (pin "1") (pinfunction "1_1") (pintype "passive"))
    )
    (net (code "68") (name "Net-(DD13-FPR7{slash}sD2)") (class "Default")
      (node (ref "DD13") (pin "31") (pinfunction "FPR7/sD2_31") (pintype "passive"))
      (node (ref "R82") (pin "1") (pinfunction "1_1") (pintype "passive"))
    )
    (net (code "69") (name "Net-(DD13-GPIO1{slash}TCLP{slash}FPG0)") (class "Default")
      (node (ref "DD13") (pin "20") (pinfunction "GPIO1/TCLP/FPG0_20") (pintype "passive"))
      (node (ref "R83") (pin "1") (pinfunction "1_1") (pintype "passive"))
    )
    (net (code "70") (name "Net-(DD13-GPIO2{slash}TRUDL{slash}FPG1)") (class "Default")
      (node (ref "DD13") (pin "21") (pinfunction "GPIO2/TRUDL/FPG1_21") (pintype "passive"))
      (node (ref "R84") (pin "1") (pinfunction "1_1") (pintype "passive"))
    )
    (net (code "71") (name "Net-(DD13-GPIO3{slash}TRCLK{slash}FPR0)") (class "Default")
      (node (ref "DD13") (pin "23") (pinfunction "GPIO3/TRCLK/FPR0_23") (pintype "passive"))
      (node (ref "R75") (pin "1") (pinfunction "1_1") (pintype "passive"))
    )
    (net (code "72") (name "Net-(DD13-GPIO4{slash}TCLRL{slash}FPR1)") (class "Default")
      (node (ref "DD13") (pin "24") (pinfunction "GPIO4/TCLRL/FPR1_24") (pintype "passive"))
      (node (ref "R76") (pin "1") (pinfunction "1_1") (pintype "passive"))
    )
    (net (code "73") (name "Net-(DD13-PWM1{slash}TRSPB{slash}FPB0)") (class "Default")
      (node (ref "DD13") (pin "17") (pinfunction "PWM1/TRSPB/FPB0_17") (pintype "passive"))
      (node (ref "R91") (pin "1") (pinfunction "1_1") (pintype "passive"))
    )
    (net (code "74") (name "Net-(DD13-PWM2{slash}TCSPR{slash}FPB1)") (class "Default")
      (node (ref "DD13") (pin "19") (pinfunction "PWM2/TCSPR/FPB1_19") (pintype "passive"))
      (node (ref "R92") (pin "1") (pinfunction "1_1") (pintype "passive"))
    )
    (net (code "75") (name "Net-(DD13-TCCLK{slash}sCLK{slash}FPCLK)") (class "Default")
      (node (ref "DD13") (pin "13") (pinfunction "TCCLK/sCLK/FPCLK_13") (pintype "passive"))
      (node (ref "R101") (pin "1") (pinfunction "1_1") (pintype "passive"))
    )
    (net (code "76") (name "Net-(DD13-TCSPL{slash}sHS{slash}FPHS)") (class "Default")
      (node (ref "DD13") (pin "15") (pinfunction "TCSPL/sHS/FPHS_15") (pintype "passive"))
      (node (ref "R103") (pin "1") (pinfunction "1_1") (pintype "passive"))
    )
    (net (code "77") (name "Net-(DD13-TROE{slash}sDE{slash}FPDE)") (class "Default")
      (node (ref "DD13") (pin "16") (pinfunction "TROE/sDE/FPDE_16") (pintype "passive"))
      (node (ref "R104") (pin "1") (pinfunction "1_1") (pintype "passive"))
    )
    (net (code "78") (name "Net-(DD13-TRSPT{slash}sVS{slash}FPVS)") (class "Default")
      (node (ref "DD13") (pin "14") (pinfunction "TRSPT/sVS/FPVS_14") (pintype "passive"))
      (node (ref "R102") (pin "1") (pinfunction "1_1") (pintype "passive"))
    )
    (net (code "79") (name "Net-(DD13-XTI)") (class "Default")
      (node (ref "BQ3") (pin "1") (pinfunction "1_1") (pintype "passive"))
      (node (ref "C126") (pin "2") (pinfunction "2_2") (pintype "passive"))
      (node (ref "DD13") (pin "10") (pinfunction "XTI_10") (pintype "passive"))
      (node (ref "R106") (pin "1") (pinfunction "1_1") (pintype "passive"))
    )
    (net (code "80") (name "Net-(DD13-XTO)") (class "Default")
      (node (ref "DD13") (pin "11") (pinfunction "XTO_11") (pintype "passive"))
      (node (ref "R105") (pin "2") (pinfunction "2_2") (pintype "passive"))
      (node (ref "R106") (pin "2") (pinfunction "2_2") (pintype "passive"))
    )
    (net (code "81") (name "VCC") (class "Default")
      (node (ref "C119") (pin "1") (pinfunction "1_1") (pintype "passive"))
      (node (ref "C122") (pin "1") (pinfunction "1_1") (pintype "passive"))
      (node (ref "DD13") (pin "18") (pinfunction "VDD33_18") (pintype "passive"))
      (node (ref "DD13") (pin "37") (pinfunction "VDD33_37") (pintype "passive"))
    )
    (net (code "82") (name "VDD18") (class "Default")
      (node (ref "C120") (pin "1") (pinfunction "1_1") (pintype "passive"))
      (node (ref "C121") (pin "1") (pinfunction "1_1") (pintype "passive"))
      (node (ref "DD13") (pin "22") (pinfunction "VDD18_22") (pintype "passive"))
      (node (ref "DD13") (pin "42") (pinfunction "VDD18_42") (pintype "passive"))
    )
    (net (code "83") (name "VDD_5V") (class "Default")
      (node (ref "L13") (pin "1") (pinfunction "1_1") (pintype "passive"))
    )
    (net (code "84") (name "unconnected-(DD13-MPO-Pad12)") (class "Default")
      (node (ref "DD13") (pin "12") (pinfunction "MPO_12") (pintype "passive"))
    )
    (net (code "85") (name "unconnected-(VD14-Pad3)") (class "Default")
      (node (ref "VD14") (pin "3") (pinfunction "3_3") (pintype "passive"))
    )
    (net (code "86") (name "unconnected-(VD15-Pad3)") (class "Default")
      (node (ref "VD15") (pin "3") (pinfunction "3_3") (pintype "passive"))
    )
    (net (code "87") (name "unconnected-(VD16-Pad3)") (class "Default")
      (node (ref "VD16") (pin "3") (pinfunction "3_3") (pintype "passive"))
    )
    (net (code "88") (name "unconnected-(VD17-Pad3)") (class "Default")
      (node (ref "VD17") (pin "3") (pinfunction "3_3") (pintype "passive"))
    )
  )
)
